# led.net
KiCad netlist of a schematic drawn in Altium Designer
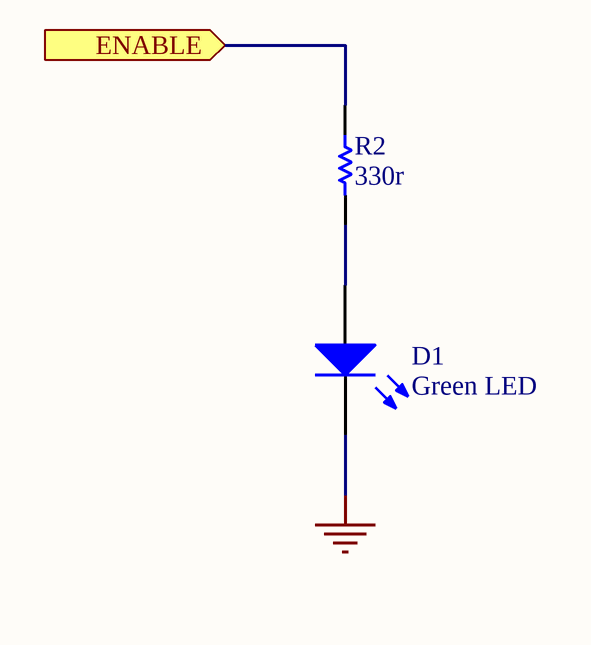
[diagram p0: led.SchDoc]

(export (version "E")
  (design (tool "Eeschema 10.0.6"))
  (components
    (comp (ref "D1")
      (value "Green LED")
      (footprint "LED 0805")
      (description "Typical INFRARED GaAs LED")
      (fields (field (name "PUBLISHER") "Altium Limited"))
      (libsource (lib "Miscellaneous Devices") (part "LED0"))
    )
    (comp (ref "R2")
      (value "330r")
      (footprint "RESC1608N")
      (description "Resistor")
      (fields (field (name "PUBLISHER") "Altium Limited"))
      (libsource (lib "Miscellaneous Devices") (part "Res1"))
    )
  )
  (nets
    (net (code "1") (name "/ENABLE") (class "Default")
      (node (ref "R2") (pin "1") (pinfunction "1_1") (pintype "passive"))
    )
    (net (code "2") (name "GND") (class "Default")
      (node (ref "D1") (pin "2") (pinfunction "K_2") (pintype "passive"))
    )
    (net (code "3") (name "Net-(D1-A)") (class "Default")
      (node (ref "D1") (pin "1") (pinfunction "A_1") (pintype "passive"))
      (node (ref "R2") (pin "2") (pinfunction "2_2") (pintype "passive"))
    )
  )
)
